# Stromcek_v1_0.net
KiCad netlist of a schematic drawn in EAGLE
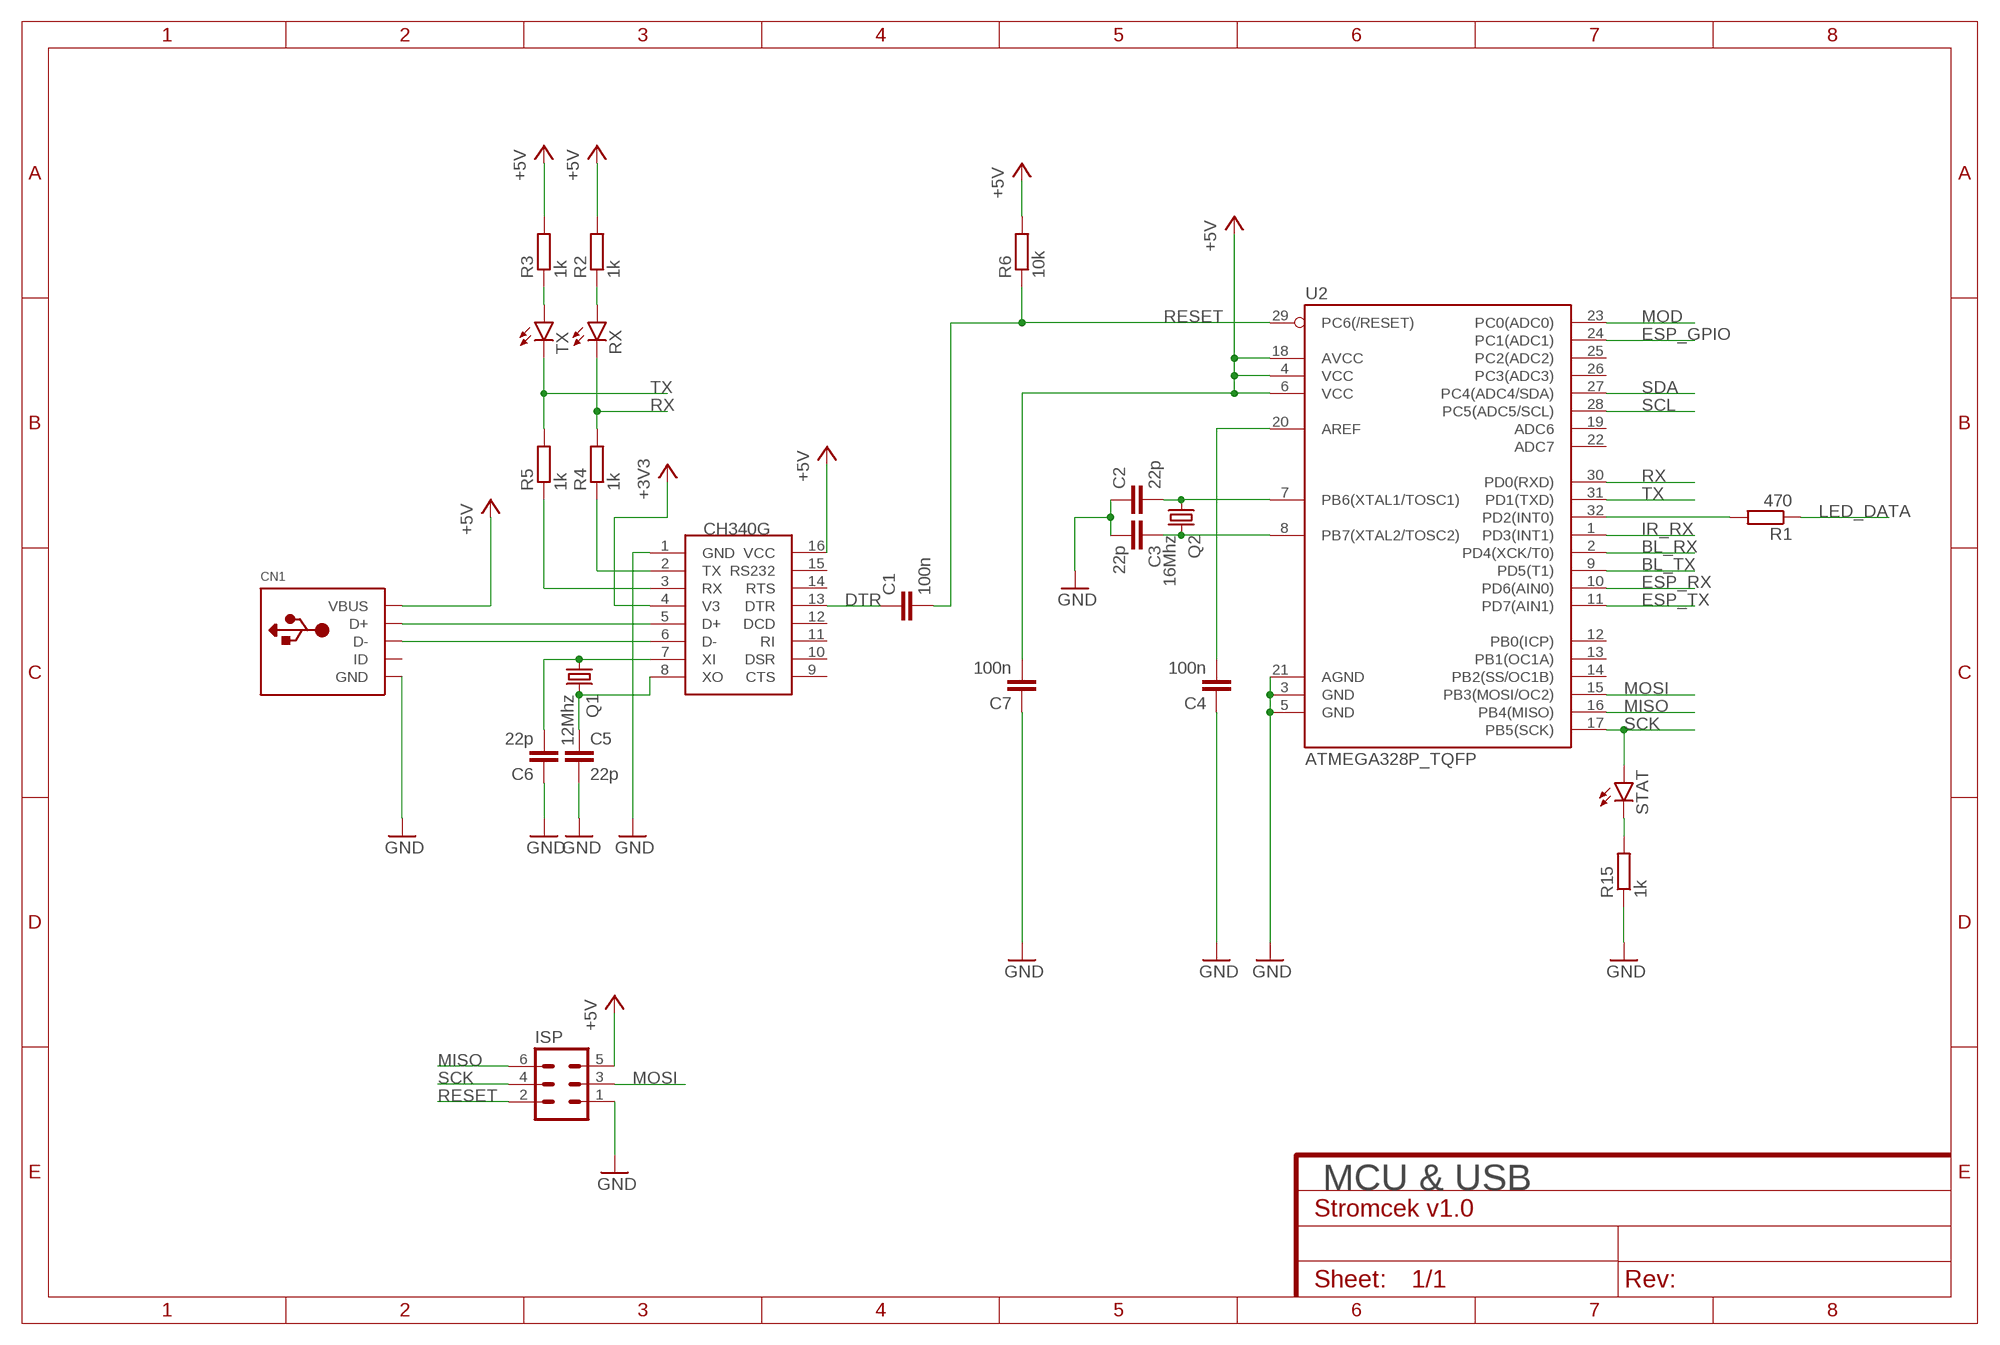
[diagram p0: schematic, sheet 1, part 1 of 2]
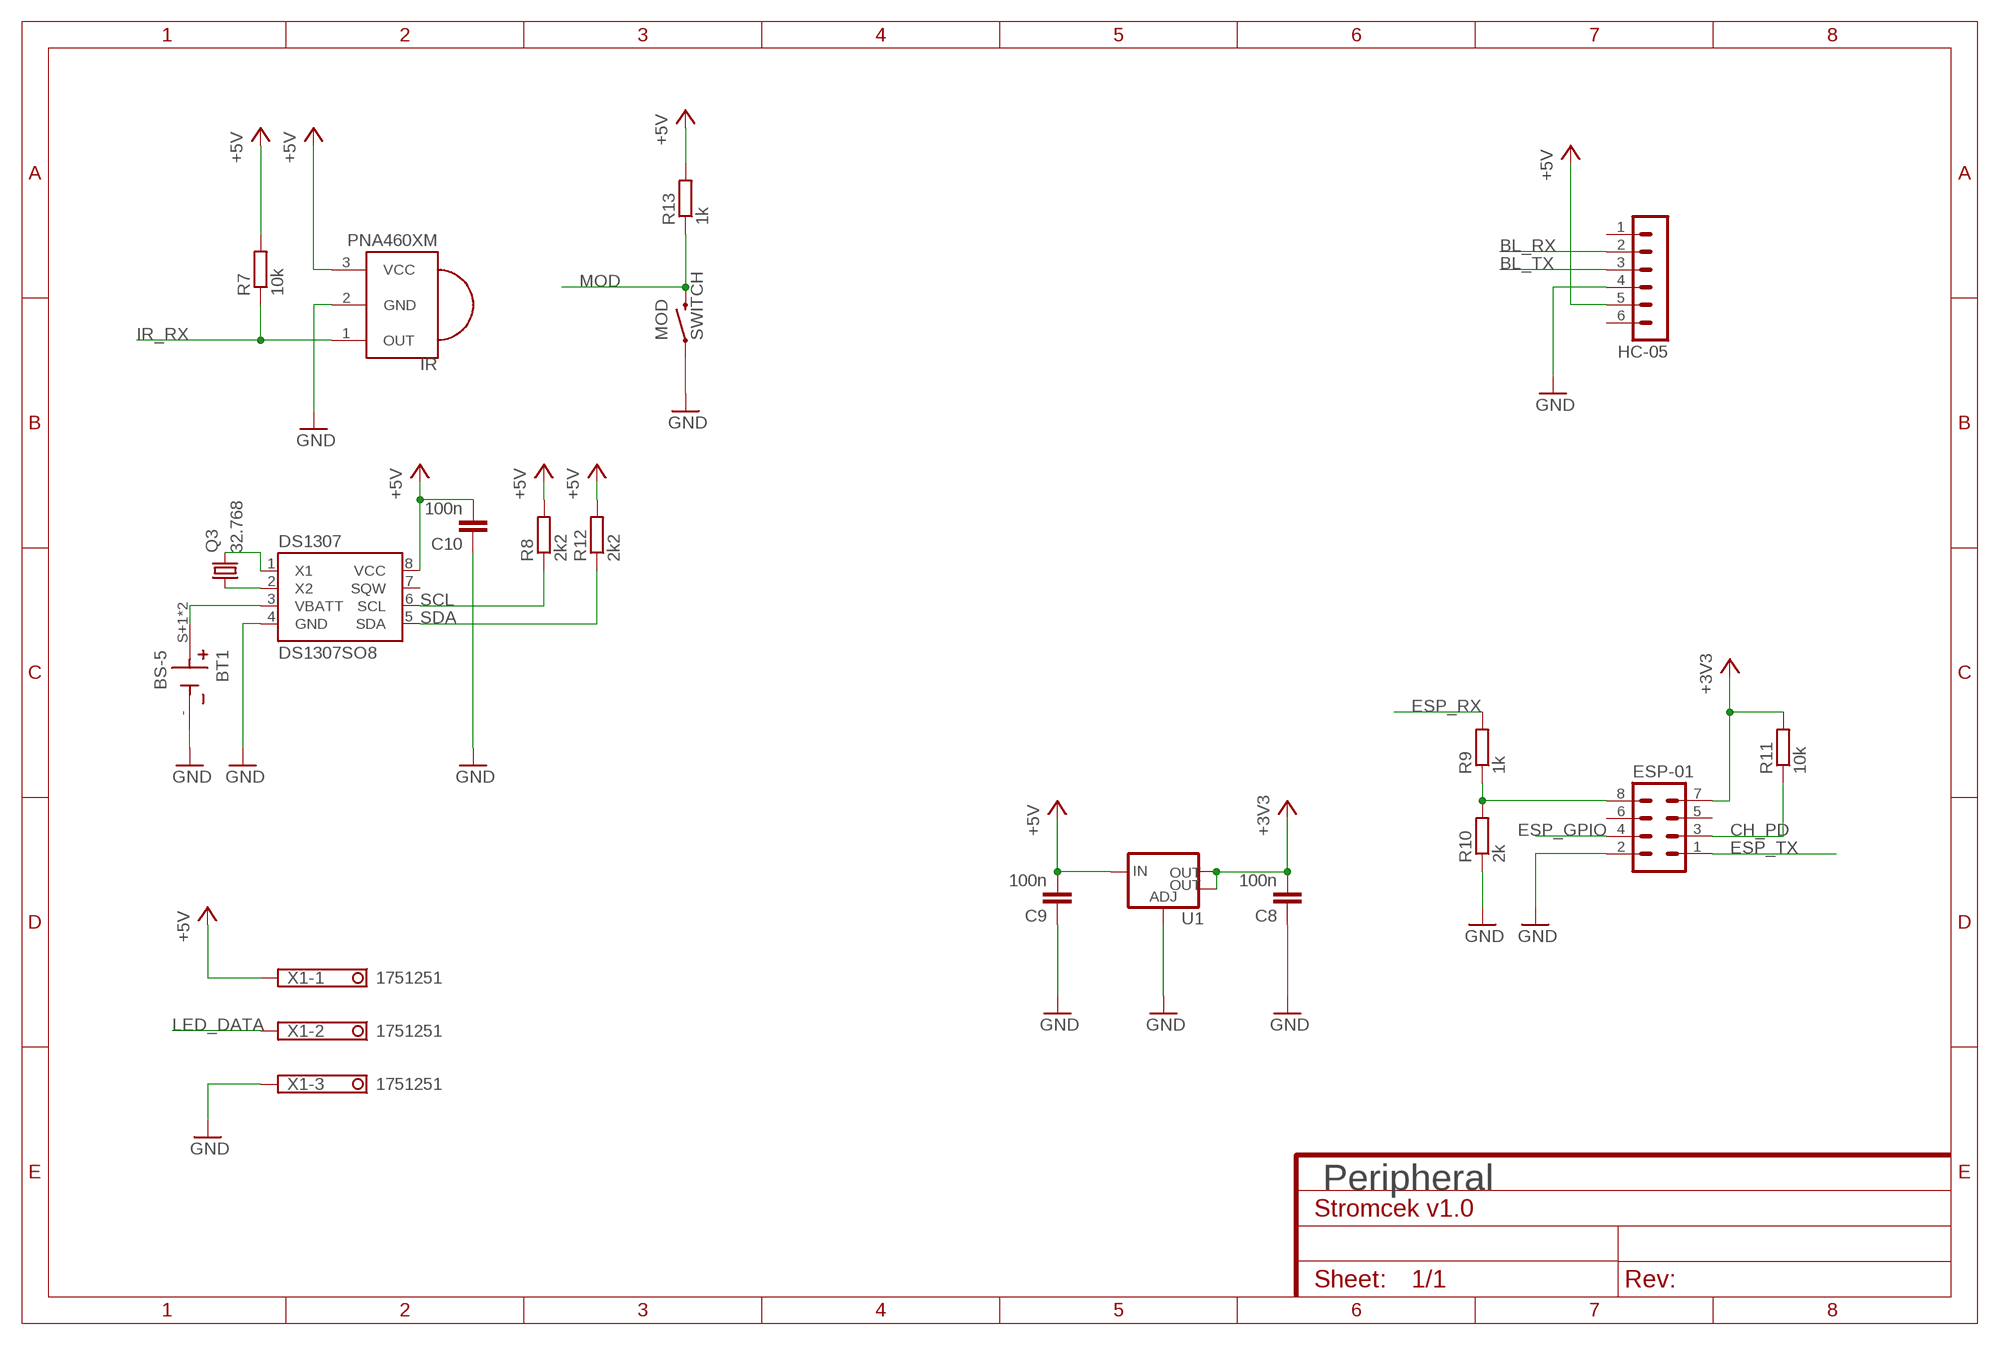
[diagram p1: schematic, sheet 1, part 2 of 2]

(export (version "E")
  (design (tool "Eeschema 10.0.6"))
  (components
    (comp (ref "BT1")
      (value "BS-5")
      (footprint "eagle-import:BAT_BS-5")
      (fields (field (name "MF") "MPD"))
      (libsource (lib "eagle-import") (part "BS-5"))
    )
    (comp (ref "C1")
      (value "100n")
      (footprint "eagle-import:C0603")
      (libsource (lib "eagle-import") (part "C-EUC0603"))
    )
    (comp (ref "C2")
      (value "22p")
      (footprint "eagle-import:C0603")
      (libsource (lib "eagle-import") (part "C-EUC0603"))
    )
    (comp (ref "C3")
      (value "22p")
      (footprint "eagle-import:C0603")
      (libsource (lib "eagle-import") (part "C-EUC0603"))
    )
    (comp (ref "C4")
      (value "100n")
      (footprint "eagle-import:C0603")
      (libsource (lib "eagle-import") (part "C-EUC0603"))
    )
    (comp (ref "C5")
      (value "22p")
      (footprint "eagle-import:C0603")
      (libsource (lib "eagle-import") (part "C-EUC0603"))
    )
    (comp (ref "C6")
      (value "22p")
      (footprint "eagle-import:C0603")
      (libsource (lib "eagle-import") (part "C-EUC0603"))
    )
    (comp (ref "C7")
      (value "100n")
      (footprint "eagle-import:C0603")
      (libsource (lib "eagle-import") (part "C-EUC0603"))
    )
    (comp (ref "C8")
      (value "100n")
      (footprint "eagle-import:C0603")
      (libsource (lib "eagle-import") (part "C-EUC0603"))
    )
    (comp (ref "C9")
      (value "100n")
      (footprint "eagle-import:C0603")
      (libsource (lib "eagle-import") (part "C-EUC0603"))
    )
    (comp (ref "C10")
      (value "100n")
      (footprint "eagle-import:C0603")
      (libsource (lib "eagle-import") (part "C-EUC0603"))
    )
    (comp (ref "CN1")
      (value "USBMOLEX")
      (footprint "eagle-import:USB-MINIB-THM-MOLEX")
      (libsource (lib "eagle-import") (part "USBMOLEX"))
    )
    (comp (ref "DS1307")
      (value "DS1307SO8")
      (footprint "eagle-import:SO08")
      (libsource (lib "eagle-import") (part "DS1307SO8"))
    )
    (comp (ref "ESP-01")
      (value "MA04-2")
      (footprint "eagle-import:MA04-2")
      (libsource (lib "eagle-import") (part "MA04-2"))
    )
    (comp (ref "HC-05")
      (value "MA06-1")
      (footprint "eagle-import:MA06-1")
      (libsource (lib "eagle-import") (part "MA06-1"))
    )
    (comp (ref "IR")
      (value "PNA460XM")
      (footprint "eagle-import:PNA460XM")
      (libsource (lib "eagle-import") (part "PNA460XM"))
    )
    (comp (ref "ISP")
      (value "MA03-2")
      (footprint "eagle-import:MA03-2")
      (libsource (lib "eagle-import") (part "MA03-2"))
    )
    (comp (ref "MOD")
      (value "SWITCH")
      (footprint "eagle-import:TACTILE-PTH-EZ")
      (libsource (lib "eagle-import") (part "SWITCH-MOMENTARY-2PTH_EZ"))
    )
    (comp (ref "Q1")
      (value "12Mhz")
      (footprint "eagle-import:HC49UP")
      (libsource (lib "eagle-import") (part "CRYSTALHC49UP"))
    )
    (comp (ref "Q2")
      (value "16Mhz")
      (footprint "eagle-import:HC49UP")
      (libsource (lib "eagle-import") (part "CRYSTALHC49UP"))
    )
    (comp (ref "Q3")
      (value "32.768")
      (footprint "eagle-import:TC26")
      (libsource (lib "eagle-import") (part "CRYSTALTC26"))
    )
    (comp (ref "R1")
      (value "470")
      (footprint "eagle-import:R0603")
      (libsource (lib "eagle-import") (part "R-EU_R0603"))
    )
    (comp (ref "R2")
      (value "1k")
      (footprint "eagle-import:R0603")
      (libsource (lib "eagle-import") (part "R-EU_R0603"))
    )
    (comp (ref "R3")
      (value "1k")
      (footprint "eagle-import:R0603")
      (libsource (lib "eagle-import") (part "R-EU_R0603"))
    )
    (comp (ref "R4")
      (value "1k")
      (footprint "eagle-import:R0603")
      (libsource (lib "eagle-import") (part "R-EU_R0603"))
    )
    (comp (ref "R5")
      (value "1k")
      (footprint "eagle-import:R0603")
      (libsource (lib "eagle-import") (part "R-EU_R0603"))
    )
    (comp (ref "R6")
      (value "10k")
      (footprint "eagle-import:R0603")
      (libsource (lib "eagle-import") (part "R-EU_R0603"))
    )
    (comp (ref "R7")
      (value "10k")
      (footprint "eagle-import:R0603")
      (libsource (lib "eagle-import") (part "R-EU_R0603"))
    )
    (comp (ref "R8")
      (value "2k2")
      (footprint "eagle-import:R0603")
      (libsource (lib "eagle-import") (part "R-EU_R0603"))
    )
    (comp (ref "R9")
      (value "1k")
      (footprint "eagle-import:R0603")
      (libsource (lib "eagle-import") (part "R-EU_R0603"))
    )
    (comp (ref "R10")
      (value "2k")
      (footprint "eagle-import:R0603")
      (libsource (lib "eagle-import") (part "R-EU_R0603"))
    )
    (comp (ref "R11")
      (value "10k")
      (footprint "eagle-import:R0603")
      (libsource (lib "eagle-import") (part "R-EU_R0603"))
    )
    (comp (ref "R12")
      (value "2k2")
      (footprint "eagle-import:R0603")
      (libsource (lib "eagle-import") (part "R-EU_R0603"))
    )
    (comp (ref "R13")
      (value "1k")
      (footprint "eagle-import:R0603")
      (libsource (lib "eagle-import") (part "resistor_R-EU_R0603"))
    )
    (comp (ref "R15")
      (value "1k")
      (footprint "eagle-import:R0603")
      (libsource (lib "eagle-import") (part "R-EU_R0603"))
    )
    (comp (ref "RX")
      (value "LEDSML0805")
      (footprint "eagle-import:SML0805")
      (libsource (lib "eagle-import") (part "LEDSML0805"))
    )
    (comp (ref "STAT")
      (value "LEDSML0805")
      (footprint "eagle-import:SML0805")
      (libsource (lib "eagle-import") (part "LEDSML0805"))
    )
    (comp (ref "TX")
      (value "LEDSML0805")
      (footprint "eagle-import:SML0805")
      (libsource (lib "eagle-import") (part "LEDSML0805"))
    )
    (comp (ref "U$1")
      (value "CH340G")
      (footprint "eagle-import:SOIC16")
      (libsource (lib "eagle-import") (part "CH340G"))
    )
    (comp (ref "U1")
      (value "V_REG_LM1117SOT223")
      (footprint "eagle-import:SOT223")
      (libsource (lib "eagle-import") (part "V_REG_LM1117SOT223"))
    )
    (comp (ref "U2")
      (value "ATMEGA328P_TQFP")
      (footprint "eagle-import:TQFP32-08")
      (libsource (lib "eagle-import") (part "ATMEGA328P_TQFP"))
    )
    (comp (ref "X1")
      (value "1751251")
      (footprint "eagle-import:1751251")
      (libsource (lib "eagle-import") (part "1751251"))
    )
  )
  (nets
    (net (code "1") (name "+3V3") (class "Default")
      (node (ref "C8") (pin "2") (pinfunction "2_2") (pintype "passive"))
      (node (ref "ESP-01") (pin "7") (pinfunction "7_7") (pintype "passive"))
      (node (ref "R11") (pin "2") (pinfunction "2_2") (pintype "passive"))
      (node (ref "U$1") (pin "4") (pinfunction "V3_4") (pintype "bidirectional"))
      (node (ref "U1") (pin "2") (pinfunction "OUT_2") (pintype "output"))
      (node (ref "U1") (pin "4") (pinfunction "OUT_4") (pintype "output"))
    )
    (net (code "2") (name "+5V") (class "Default")
      (node (ref "C10") (pin "2") (pinfunction "2_2") (pintype "passive"))
      (node (ref "C7") (pin "2") (pinfunction "2_2") (pintype "passive"))
      (node (ref "C9") (pin "2") (pinfunction "2_2") (pintype "passive"))
      (node (ref "CN1") (pin "VBUS") (pinfunction "VBUS_VBUS") (pintype "power_in"))
      (node (ref "DS1307") (pin "8") (pinfunction "VCC_8") (pintype "bidirectional"))
      (node (ref "HC-05") (pin "5") (pinfunction "5_5") (pintype "passive"))
      (node (ref "IR") (pin "3") (pinfunction "VCC_3") (pintype "power_in"))
      (node (ref "ISP") (pin "5") (pinfunction "5_5") (pintype "passive"))
      (node (ref "R12") (pin "2") (pinfunction "2_2") (pintype "passive"))
      (node (ref "R13") (pin "2") (pinfunction "2_2") (pintype "passive"))
      (node (ref "R2") (pin "2") (pinfunction "2_2") (pintype "passive"))
      (node (ref "R3") (pin "2") (pinfunction "2_2") (pintype "passive"))
      (node (ref "R6") (pin "2") (pinfunction "2_2") (pintype "passive"))
      (node (ref "R7") (pin "2") (pinfunction "2_2") (pintype "passive"))
      (node (ref "R8") (pin "2") (pinfunction "2_2") (pintype "passive"))
      (node (ref "U$1") (pin "16") (pinfunction "VCC_16") (pintype "bidirectional"))
      (node (ref "U1") (pin "3") (pinfunction "IN_3") (pintype "input"))
      (node (ref "U2") (pin "18") (pinfunction "AVCC_18") (pintype "bidirectional"))
      (node (ref "U2") (pin "4") (pinfunction "VCC_4") (pintype "bidirectional"))
      (node (ref "U2") (pin "6") (pinfunction "VCC_6") (pintype "bidirectional"))
      (node (ref "X1") (pin "1") (pinfunction "K_1") (pintype "passive"))
    )
    (net (code "3") (name "/BL_RX") (class "Default")
      (node (ref "HC-05") (pin "2") (pinfunction "2_2") (pintype "passive"))
      (node (ref "U2") (pin "2") (pinfunction "PD4(XCK/T0)_2") (pintype "bidirectional"))
    )
    (net (code "4") (name "/BL_TX") (class "Default")
      (node (ref "HC-05") (pin "3") (pinfunction "3_3") (pintype "passive"))
      (node (ref "U2") (pin "9") (pinfunction "PD5(T1)_9") (pintype "bidirectional"))
    )
    (net (code "5") (name "/CH_PD") (class "Default")
      (node (ref "ESP-01") (pin "3") (pinfunction "3_3") (pintype "passive"))
      (node (ref "R11") (pin "1") (pinfunction "1_1") (pintype "passive"))
    )
    (net (code "6") (name "/DTR") (class "Default")
      (node (ref "C1") (pin "1") (pinfunction "1_1") (pintype "passive"))
      (node (ref "U$1") (pin "13") (pinfunction "DTR_13") (pintype "bidirectional"))
    )
    (net (code "7") (name "/ESP_GPIO") (class "Default")
      (node (ref "ESP-01") (pin "4") (pinfunction "4_4") (pintype "passive"))
      (node (ref "U2") (pin "24") (pinfunction "PC1(ADC1)_24") (pintype "bidirectional"))
    )
    (net (code "8") (name "/ESP_RX") (class "Default")
      (node (ref "R9") (pin "2") (pinfunction "2_2") (pintype "passive"))
      (node (ref "U2") (pin "10") (pinfunction "PD6(AIN0)_10") (pintype "bidirectional"))
    )
    (net (code "9") (name "/ESP_TX") (class "Default")
      (node (ref "ESP-01") (pin "1") (pinfunction "1_1") (pintype "passive"))
      (node (ref "U2") (pin "11") (pinfunction "PD7(AIN1)_11") (pintype "bidirectional"))
    )
    (net (code "10") (name "/IR_RX") (class "Default")
      (node (ref "IR") (pin "1") (pinfunction "OUT_1") (pintype "output"))
      (node (ref "R7") (pin "1") (pinfunction "1_1") (pintype "passive"))
      (node (ref "U2") (pin "1") (pinfunction "PD3(INT1)_1") (pintype "bidirectional"))
    )
    (net (code "11") (name "/LED_DATA") (class "Default")
      (node (ref "R1") (pin "1") (pinfunction "1_1") (pintype "passive"))
      (node (ref "X1") (pin "2") (pinfunction "K_2") (pintype "passive"))
    )
    (net (code "12") (name "/MISO") (class "Default")
      (node (ref "ISP") (pin "6") (pinfunction "6_6") (pintype "passive"))
      (node (ref "U2") (pin "16") (pinfunction "PB4(MISO)_16") (pintype "bidirectional"))
    )
    (net (code "13") (name "/MOD") (class "Default")
      (node (ref "MOD") (pin "3") (pinfunction "2_3") (pintype "passive"))
      (node (ref "R13") (pin "1") (pinfunction "1_1") (pintype "passive"))
      (node (ref "U2") (pin "23") (pinfunction "PC0(ADC0)_23") (pintype "bidirectional"))
    )
    (net (code "14") (name "/MOSI") (class "Default")
      (node (ref "ISP") (pin "3") (pinfunction "3_3") (pintype "passive"))
      (node (ref "U2") (pin "15") (pinfunction "PB3(MOSI/OC2)_15") (pintype "bidirectional"))
    )
    (net (code "15") (name "/RESET") (class "Default")
      (node (ref "C1") (pin "2") (pinfunction "2_2") (pintype "passive"))
      (node (ref "ISP") (pin "2") (pinfunction "2_2") (pintype "passive"))
      (node (ref "R6") (pin "1") (pinfunction "1_1") (pintype "passive"))
      (node (ref "U2") (pin "29") (pinfunction "PC6(/RESET)_29") (pintype "bidirectional"))
    )
    (net (code "16") (name "/RX") (class "Default")
      (node (ref "R4") (pin "2") (pinfunction "2_2") (pintype "passive"))
      (node (ref "RX") (pin "C") (pinfunction "C_C") (pintype "passive"))
      (node (ref "U2") (pin "30") (pinfunction "PD0(RXD)_30") (pintype "bidirectional"))
    )
    (net (code "17") (name "/SCK") (class "Default")
      (node (ref "ISP") (pin "4") (pinfunction "4_4") (pintype "passive"))
      (node (ref "STAT") (pin "A") (pinfunction "A_A") (pintype "passive"))
      (node (ref "U2") (pin "17") (pinfunction "PB5(SCK)_17") (pintype "bidirectional"))
    )
    (net (code "18") (name "/SCL") (class "Default")
      (node (ref "DS1307") (pin "6") (pinfunction "SCL_6") (pintype "bidirectional"))
      (node (ref "R8") (pin "1") (pinfunction "1_1") (pintype "passive"))
      (node (ref "U2") (pin "28") (pinfunction "PC5(ADC5/SCL)_28") (pintype "bidirectional"))
    )
    (net (code "19") (name "/SDA") (class "Default")
      (node (ref "DS1307") (pin "5") (pinfunction "SDA_5") (pintype "bidirectional"))
      (node (ref "R12") (pin "1") (pinfunction "1_1") (pintype "passive"))
      (node (ref "U2") (pin "27") (pinfunction "PC4(ADC4/SDA)_27") (pintype "bidirectional"))
    )
    (net (code "20") (name "/TX") (class "Default")
      (node (ref "R5") (pin "2") (pinfunction "2_2") (pintype "passive"))
      (node (ref "TX") (pin "C") (pinfunction "C_C") (pintype "passive"))
      (node (ref "U2") (pin "31") (pinfunction "PD1(TXD)_31") (pintype "bidirectional"))
    )
    (net (code "21") (name "GND") (class "Default")
      (node (ref "BT1") (pin "-") (pinfunction "-_-") (pintype "passive"))
      (node (ref "C10") (pin "1") (pinfunction "1_1") (pintype "passive"))
      (node (ref "C2") (pin "1") (pinfunction "1_1") (pintype "passive"))
      (node (ref "C3") (pin "2") (pinfunction "2_2") (pintype "passive"))
      (node (ref "C4") (pin "1") (pinfunction "1_1") (pintype "passive"))
      (node (ref "C5") (pin "2") (pinfunction "2_2") (pintype "passive"))
      (node (ref "C6") (pin "1") (pinfunction "1_1") (pintype "passive"))
      (node (ref "C7") (pin "1") (pinfunction "1_1") (pintype "passive"))
      (node (ref "C8") (pin "1") (pinfunction "1_1") (pintype "passive"))
      (node (ref "C9") (pin "1") (pinfunction "1_1") (pintype "passive"))
      (node (ref "CN1") (pin "GND") (pinfunction "GND_GND") (pintype "power_in"))
      (node (ref "CN1") (pin "GND1") (pinfunction "GND_GND1") (pintype "power_in"))
      (node (ref "CN1") (pin "GND4") (pinfunction "GND_GND4") (pintype "power_in"))
      (node (ref "DS1307") (pin "4") (pinfunction "GND_4") (pintype "bidirectional"))
      (node (ref "ESP-01") (pin "2") (pinfunction "2_2") (pintype "passive"))
      (node (ref "HC-05") (pin "4") (pinfunction "4_4") (pintype "passive"))
      (node (ref "IR") (pin "2") (pinfunction "GND_2") (pintype "power_in"))
      (node (ref "ISP") (pin "1") (pinfunction "1_1") (pintype "passive"))
      (node (ref "MOD") (pin "1") (pinfunction "1_1") (pintype "passive"))
      (node (ref "R10") (pin "1") (pinfunction "1_1") (pintype "passive"))
      (node (ref "R15") (pin "1") (pinfunction "1_1") (pintype "passive"))
      (node (ref "U$1") (pin "1") (pinfunction "GND_1") (pintype "bidirectional"))
      (node (ref "U1") (pin "1") (pinfunction "ADJ_1") (pintype "input"))
      (node (ref "U2") (pin "21") (pinfunction "AGND_21") (pintype "bidirectional"))
      (node (ref "U2") (pin "3") (pinfunction "GND_3") (pintype "bidirectional"))
      (node (ref "U2") (pin "5") (pinfunction "GND_5") (pintype "bidirectional"))
      (node (ref "X1") (pin "3") (pinfunction "K_3") (pintype "passive"))
    )
    (net (code "22") (name "Net-(DS1307-VBATT)") (class "Default")
      (node (ref "BT1") (pin "S+1") (pinfunction "+_S+1") (pintype "passive"))
      (node (ref "BT1") (pin "S+2") (pinfunction "+_S+2") (pintype "passive"))
      (node (ref "DS1307") (pin "3") (pinfunction "VBATT_3") (pintype "bidirectional"))
    )
    (net (code "23") (name "Net-(DS1307-X1)") (class "Default")
      (node (ref "DS1307") (pin "1") (pinfunction "X1_1") (pintype "bidirectional"))
      (node (ref "Q3") (pin "2") (pinfunction "2_2") (pintype "passive"))
    )
    (net (code "24") (name "Net-(DS1307-X2)") (class "Default")
      (node (ref "DS1307") (pin "2") (pinfunction "X2_2") (pintype "bidirectional"))
      (node (ref "Q3") (pin "1") (pinfunction "1_1") (pintype "passive"))
    )
    (net (code "25") (name "Net-(ESP-01-Pad8)") (class "Default")
      (node (ref "ESP-01") (pin "8") (pinfunction "8_8") (pintype "passive"))
      (node (ref "R10") (pin "2") (pinfunction "2_2") (pintype "passive"))
      (node (ref "R9") (pin "1") (pinfunction "1_1") (pintype "passive"))
    )
    (net (code "26") (name "Net-(R2-Pad1)") (class "Default")
      (node (ref "R2") (pin "1") (pinfunction "1_1") (pintype "passive"))
      (node (ref "RX") (pin "A") (pinfunction "A_A") (pintype "passive"))
    )
    (net (code "27") (name "Net-(R3-Pad1)") (class "Default")
      (node (ref "R3") (pin "1") (pinfunction "1_1") (pintype "passive"))
      (node (ref "TX") (pin "A") (pinfunction "A_A") (pintype "passive"))
    )
    (net (code "28") (name "Net-(R15-Pad2)") (class "Default")
      (node (ref "R15") (pin "2") (pinfunction "2_2") (pintype "passive"))
      (node (ref "STAT") (pin "C") (pinfunction "C_C") (pintype "passive"))
    )
    (net (code "29") (name "Net-(U$1-D+)") (class "Default")
      (node (ref "CN1") (pin "D+") (pinfunction "D+_D+") (pintype "bidirectional"))
      (node (ref "U$1") (pin "5") (pinfunction "D+_5") (pintype "bidirectional"))
    )
    (net (code "30") (name "Net-(U$1-D-)") (class "Default")
      (node (ref "CN1") (pin "D-") (pinfunction "D-_D-") (pintype "bidirectional"))
      (node (ref "U$1") (pin "6") (pinfunction "D-_6") (pintype "bidirectional"))
    )
    (net (code "31") (name "Net-(U$1-RX)") (class "Default")
      (node (ref "R5") (pin "1") (pinfunction "1_1") (pintype "passive"))
      (node (ref "U$1") (pin "3") (pinfunction "RX_3") (pintype "bidirectional"))
    )
    (net (code "32") (name "Net-(U$1-TX)") (class "Default")
      (node (ref "R4") (pin "1") (pinfunction "1_1") (pintype "passive"))
      (node (ref "U$1") (pin "2") (pinfunction "TX_2") (pintype "bidirectional"))
    )
    (net (code "33") (name "Net-(U$1-XI)") (class "Default")
      (node (ref "C6") (pin "2") (pinfunction "2_2") (pintype "passive"))
      (node (ref "Q1") (pin "1") (pinfunction "1_1") (pintype "passive"))
      (node (ref "U$1") (pin "7") (pinfunction "XI_7") (pintype "bidirectional"))
    )
    (net (code "34") (name "Net-(U$1-XO)") (class "Default")
      (node (ref "C5") (pin "1") (pinfunction "1_1") (pintype "passive"))
      (node (ref "Q1") (pin "2") (pinfunction "2_2") (pintype "passive"))
      (node (ref "U$1") (pin "8") (pinfunction "XO_8") (pintype "bidirectional"))
    )
    (net (code "35") (name "Net-(U2-AREF)") (class "Default")
      (node (ref "C4") (pin "2") (pinfunction "2_2") (pintype "passive"))
      (node (ref "U2") (pin "20") (pinfunction "AREF_20") (pintype "bidirectional"))
    )
    (net (code "36") (name "Net-(U2-PB6(XTAL1{slash}TOSC1))") (class "Default")
      (node (ref "C2") (pin "2") (pinfunction "2_2") (pintype "passive"))
      (node (ref "Q2") (pin "1") (pinfunction "1_1") (pintype "passive"))
      (node (ref "U2") (pin "7") (pinfunction "PB6(XTAL1/TOSC1)_7") (pintype "bidirectional"))
    )
    (net (code "37") (name "Net-(U2-PB7(XTAL2{slash}TOSC2))") (class "Default")
      (node (ref "C3") (pin "1") (pinfunction "1_1") (pintype "passive"))
      (node (ref "Q2") (pin "2") (pinfunction "2_2") (pintype "passive"))
      (node (ref "U2") (pin "8") (pinfunction "PB7(XTAL2/TOSC2)_8") (pintype "bidirectional"))
    )
    (net (code "38") (name "Net-(U2-PD2(INT0))") (class "Default")
      (node (ref "R1") (pin "2") (pinfunction "2_2") (pintype "passive"))
      (node (ref "U2") (pin "32") (pinfunction "PD2(INT0)_32") (pintype "bidirectional"))
    )
    (net (code "39") (name "unconnected-(CN1-PadID)") (class "Default")
      (node (ref "CN1") (pin "ID") (pinfunction "ID_ID") (pintype "bidirectional"))
    )
    (net (code "40") (name "unconnected-(DS1307-SQW-Pad7)") (class "Default")
      (node (ref "DS1307") (pin "7") (pinfunction "SQW_7") (pintype "bidirectional"))
    )
    (net (code "41") (name "unconnected-(ESP-01-Pad5)") (class "Default")
      (node (ref "ESP-01") (pin "5") (pinfunction "5_5") (pintype "passive"))
    )
    (net (code "42") (name "unconnected-(ESP-01-Pad6)") (class "Default")
      (node (ref "ESP-01") (pin "6") (pinfunction "6_6") (pintype "passive"))
    )
    (net (code "43") (name "unconnected-(HC-05-Pad1)") (class "Default")
      (node (ref "HC-05") (pin "1") (pinfunction "1_1") (pintype "passive"))
    )
    (net (code "44") (name "unconnected-(HC-05-Pad6)") (class "Default")
      (node (ref "HC-05") (pin "6") (pinfunction "6_6") (pintype "passive"))
    )
    (net (code "45") (name "unconnected-(U$1-CTS-Pad9)") (class "Default")
      (node (ref "U$1") (pin "9") (pinfunction "CTS_9") (pintype "bidirectional"))
    )
    (net (code "46") (name "unconnected-(U$1-DCD-Pad12)") (class "Default")
      (node (ref "U$1") (pin "12") (pinfunction "DCD_12") (pintype "bidirectional"))
    )
    (net (code "47") (name "unconnected-(U$1-DSR-Pad10)") (class "Default")
      (node (ref "U$1") (pin "10") (pinfunction "DSR_10") (pintype "bidirectional"))
    )
    (net (code "48") (name "unconnected-(U$1-RI-Pad11)") (class "Default")
      (node (ref "U$1") (pin "11") (pinfunction "RI_11") (pintype "bidirectional"))
    )
    (net (code "49") (name "unconnected-(U$1-RS232-Pad15)") (class "Default")
      (node (ref "U$1") (pin "15") (pinfunction "RS232_15") (pintype "bidirectional"))
    )
    (net (code "50") (name "unconnected-(U$1-RTS-Pad14)") (class "Default")
      (node (ref "U$1") (pin "14") (pinfunction "RTS_14") (pintype "bidirectional"))
    )
    (net (code "51") (name "unconnected-(U2-ADC6-Pad19)") (class "Default")
      (node (ref "U2") (pin "19") (pinfunction "ADC6_19") (pintype "bidirectional"))
    )
    (net (code "52") (name "unconnected-(U2-ADC7-Pad22)") (class "Default")
      (node (ref "U2") (pin "22") (pinfunction "ADC7_22") (pintype "bidirectional"))
    )
    (net (code "53") (name "unconnected-(U2-PB0(ICP)-Pad12)") (class "Default")
      (node (ref "U2") (pin "12") (pinfunction "PB0(ICP)_12") (pintype "bidirectional"))
    )
    (net (code "54") (name "unconnected-(U2-PB1(OC1A)-Pad13)") (class "Default")
      (node (ref "U2") (pin "13") (pinfunction "PB1(OC1A)_13") (pintype "bidirectional"))
    )
    (net (code "55") (name "unconnected-(U2-PB2(SS{slash}OC1B)-Pad14)") (class "Default")
      (node (ref "U2") (pin "14") (pinfunction "PB2(SS/OC1B)_14") (pintype "bidirectional"))
    )
    (net (code "56") (name "unconnected-(U2-PC2(ADC2)-Pad25)") (class "Default")
      (node (ref "U2") (pin "25") (pinfunction "PC2(ADC2)_25") (pintype "bidirectional"))
    )
    (net (code "57") (name "unconnected-(U2-PC3(ADC3)-Pad26)") (class "Default")
      (node (ref "U2") (pin "26") (pinfunction "PC3(ADC3)_26") (pintype "bidirectional"))
    )
  )
)
